# PowerConnector.net
KiCad netlist of a schematic drawn in Altium Designer
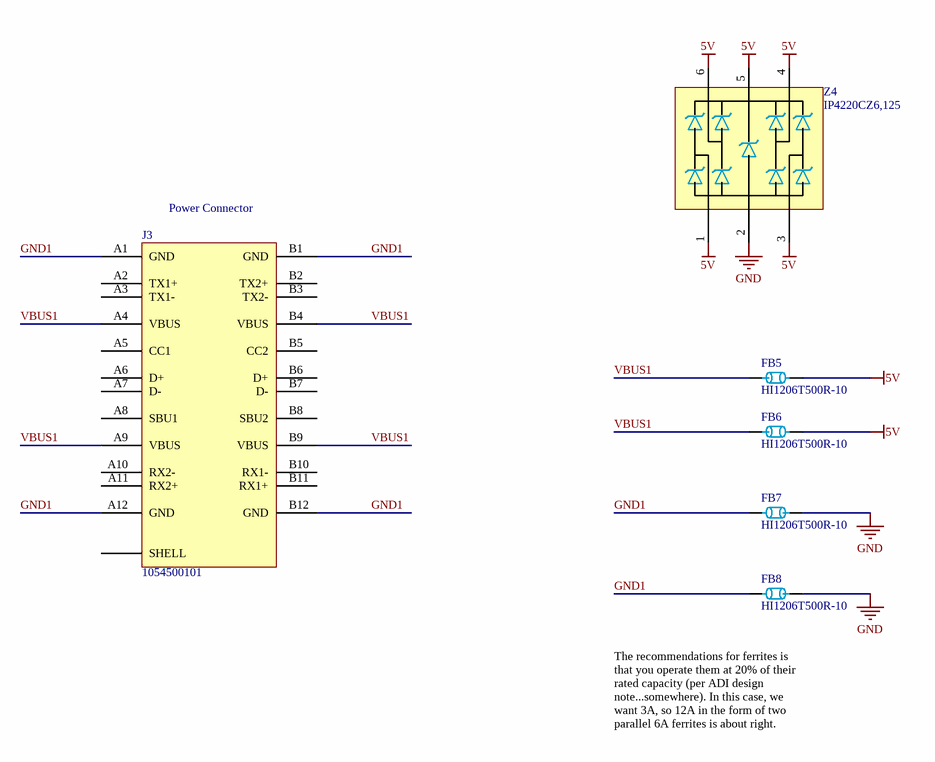
[diagram p0: PowerConnector.SchDoc]

(export (version "E")
  (design (tool "Eeschema 10.0.6"))
  (components
    (comp (ref "FB5")
      (value "HI1206T500R-10")
      (footprint "1206")
      (description "50 Ohms @ 100MHz 1 Power, Signal Line Ferrite Bead 1206 (3216 Metric) 6A 10mOhm")
      (libsource (lib "Chip_Passives") (part "HI1206T500R-10"))
    )
    (comp (ref "FB6")
      (value "HI1206T500R-10")
      (footprint "1206")
      (description "50 Ohms @ 100MHz 1 Power, Signal Line Ferrite Bead 1206 (3216 Metric) 6A 10mOhm")
      (libsource (lib "Chip_Passives") (part "HI1206T500R-10"))
    )
    (comp (ref "FB7")
      (value "HI1206T500R-10")
      (footprint "1206")
      (description "50 Ohms @ 100MHz 1 Power, Signal Line Ferrite Bead 1206 (3216 Metric) 6A 10mOhm")
      (libsource (lib "Chip_Passives") (part "HI1206T500R-10"))
    )
    (comp (ref "FB8")
      (value "HI1206T500R-10")
      (footprint "1206")
      (description "50 Ohms @ 100MHz 1 Power, Signal Line Ferrite Bead 1206 (3216 Metric) 6A 10mOhm")
      (libsource (lib "Chip_Passives") (part "HI1206T500R-10"))
    )
    (comp (ref "J3")
      (value "1054500101")
      (footprint "1054500101")
      (libsource (lib "Connectors") (part "1054500101"))
    )
    (comp (ref "Z4")
      (value "IP4220CZ6,125")
      (footprint "PESD3V3S4UD - SOT95P275X110-6N")
      (description "TVS DIODE 5.5V 6TSOP (Low capacitance, USB)")
      (libsource (lib "Diodes") (part "IP4220CZ6,125"))
    )
  )
  (nets
    (net (code "1") (name "/GND1") (class "Default")
      (node (ref "FB7") (pin "2") (pinfunction "2_2") (pintype "passive"))
      (node (ref "FB8") (pin "2") (pinfunction "2_2") (pintype "passive"))
      (node (ref "J3") (pin "A1") (pinfunction "GND_A1") (pintype "passive"))
      (node (ref "J3") (pin "A12") (pinfunction "GND_A12") (pintype "passive"))
      (node (ref "J3") (pin "B1") (pinfunction "GND_B1") (pintype "passive"))
      (node (ref "J3") (pin "B12") (pinfunction "GND_B12") (pintype "passive"))
    )
    (net (code "2") (name "/VBUS1") (class "Default")
      (node (ref "FB5") (pin "1") (pinfunction "1_1") (pintype "passive"))
      (node (ref "FB6") (pin "1") (pinfunction "1_1") (pintype "passive"))
      (node (ref "J3") (pin "A4") (pinfunction "VBUS_A4") (pintype "passive"))
      (node (ref "J3") (pin "A9") (pinfunction "VBUS_A9") (pintype "passive"))
      (node (ref "J3") (pin "B4") (pinfunction "VBUS_B4") (pintype "passive"))
      (node (ref "J3") (pin "B9") (pinfunction "VBUS_B9") (pintype "passive"))
    )
    (net (code "3") (name "5V") (class "Default")
      (node (ref "FB5") (pin "2") (pinfunction "2_2") (pintype "passive"))
      (node (ref "FB6") (pin "2") (pinfunction "2_2") (pintype "passive"))
      (node (ref "Z4") (pin "1") (pinfunction "1_1") (pintype "passive"))
      (node (ref "Z4") (pin "3") (pinfunction "3_3") (pintype "passive"))
      (node (ref "Z4") (pin "4") (pinfunction "4_4") (pintype "passive"))
      (node (ref "Z4") (pin "5") (pinfunction "5_5") (pintype "passive"))
      (node (ref "Z4") (pin "6") (pinfunction "6_6") (pintype "passive"))
    )
    (net (code "4") (name "GND") (class "Default")
      (node (ref "FB7") (pin "1") (pinfunction "1_1") (pintype "passive"))
      (node (ref "FB8") (pin "1") (pinfunction "1_1") (pintype "passive"))
      (node (ref "Z4") (pin "2") (pinfunction "2_2") (pintype "passive"))
    )
    (net (code "5") (name "unconnected-(J3-CC1-PadA5)") (class "Default")
      (node (ref "J3") (pin "A5") (pinfunction "CC1_A5") (pintype "passive"))
    )
    (net (code "6") (name "unconnected-(J3-CC2-PadB5)") (class "Default")
      (node (ref "J3") (pin "B5") (pinfunction "CC2_B5") (pintype "passive"))
    )
    (net (code "7") (name "unconnected-(J3-D+-PadA6)") (class "Default")
      (node (ref "J3") (pin "A6") (pinfunction "D+_A6") (pintype "passive"))
    )
    (net (code "8") (name "unconnected-(J3-D+-PadB6)") (class "Default")
      (node (ref "J3") (pin "B6") (pinfunction "D+_B6") (pintype "passive"))
    )
    (net (code "9") (name "unconnected-(J3-D--PadA7)") (class "Default")
      (node (ref "J3") (pin "A7") (pinfunction "D-_A7") (pintype "passive"))
    )
    (net (code "10") (name "unconnected-(J3-D--PadB7)") (class "Default")
      (node (ref "J3") (pin "B7") (pinfunction "D-_B7") (pintype "passive"))
    )
    (net (code "11") (name "unconnected-(J3-PadSHELL)") (class "Default")
      (node (ref "J3") (pin "SHELL") (pinfunction "SHELL_SHELL") (pintype "passive"))
    )
    (net (code "12") (name "unconnected-(J3-RX1+-PadB11)") (class "Default")
      (node (ref "J3") (pin "B11") (pinfunction "RX1+_B11") (pintype "passive"))
    )
    (net (code "13") (name "unconnected-(J3-RX1--PadB10)") (class "Default")
      (node (ref "J3") (pin "B10") (pinfunction "RX1-_B10") (pintype "passive"))
    )
    (net (code "14") (name "unconnected-(J3-RX2+-PadA11)") (class "Default")
      (node (ref "J3") (pin "A11") (pinfunction "RX2+_A11") (pintype "passive"))
    )
    (net (code "15") (name "unconnected-(J3-RX2--PadA10)") (class "Default")
      (node (ref "J3") (pin "A10") (pinfunction "RX2-_A10") (pintype "passive"))
    )
    (net (code "16") (name "unconnected-(J3-SBU1-PadA8)") (class "Default")
      (node (ref "J3") (pin "A8") (pinfunction "SBU1_A8") (pintype "passive"))
    )
    (net (code "17") (name "unconnected-(J3-SBU2-PadB8)") (class "Default")
      (node (ref "J3") (pin "B8") (pinfunction "SBU2_B8") (pintype "passive"))
    )
    (net (code "18") (name "unconnected-(J3-TX1+-PadA2)") (class "Default")
      (node (ref "J3") (pin "A2") (pinfunction "TX1+_A2") (pintype "passive"))
    )
    (net (code "19") (name "unconnected-(J3-TX1--PadA3)") (class "Default")
      (node (ref "J3") (pin "A3") (pinfunction "TX1-_A3") (pintype "passive"))
    )
    (net (code "20") (name "unconnected-(J3-TX2+-PadB2)") (class "Default")
      (node (ref "J3") (pin "B2") (pinfunction "TX2+_B2") (pintype "passive"))
    )
    (net (code "21") (name "unconnected-(J3-TX2--PadB3)") (class "Default")
      (node (ref "J3") (pin "B3") (pinfunction "TX2-_B3") (pintype "passive"))
    )
  )
)
